# 07_-_5V_VOLTAGE_REGULATOR.net
KiCad netlist of a schematic drawn in Altium Designer
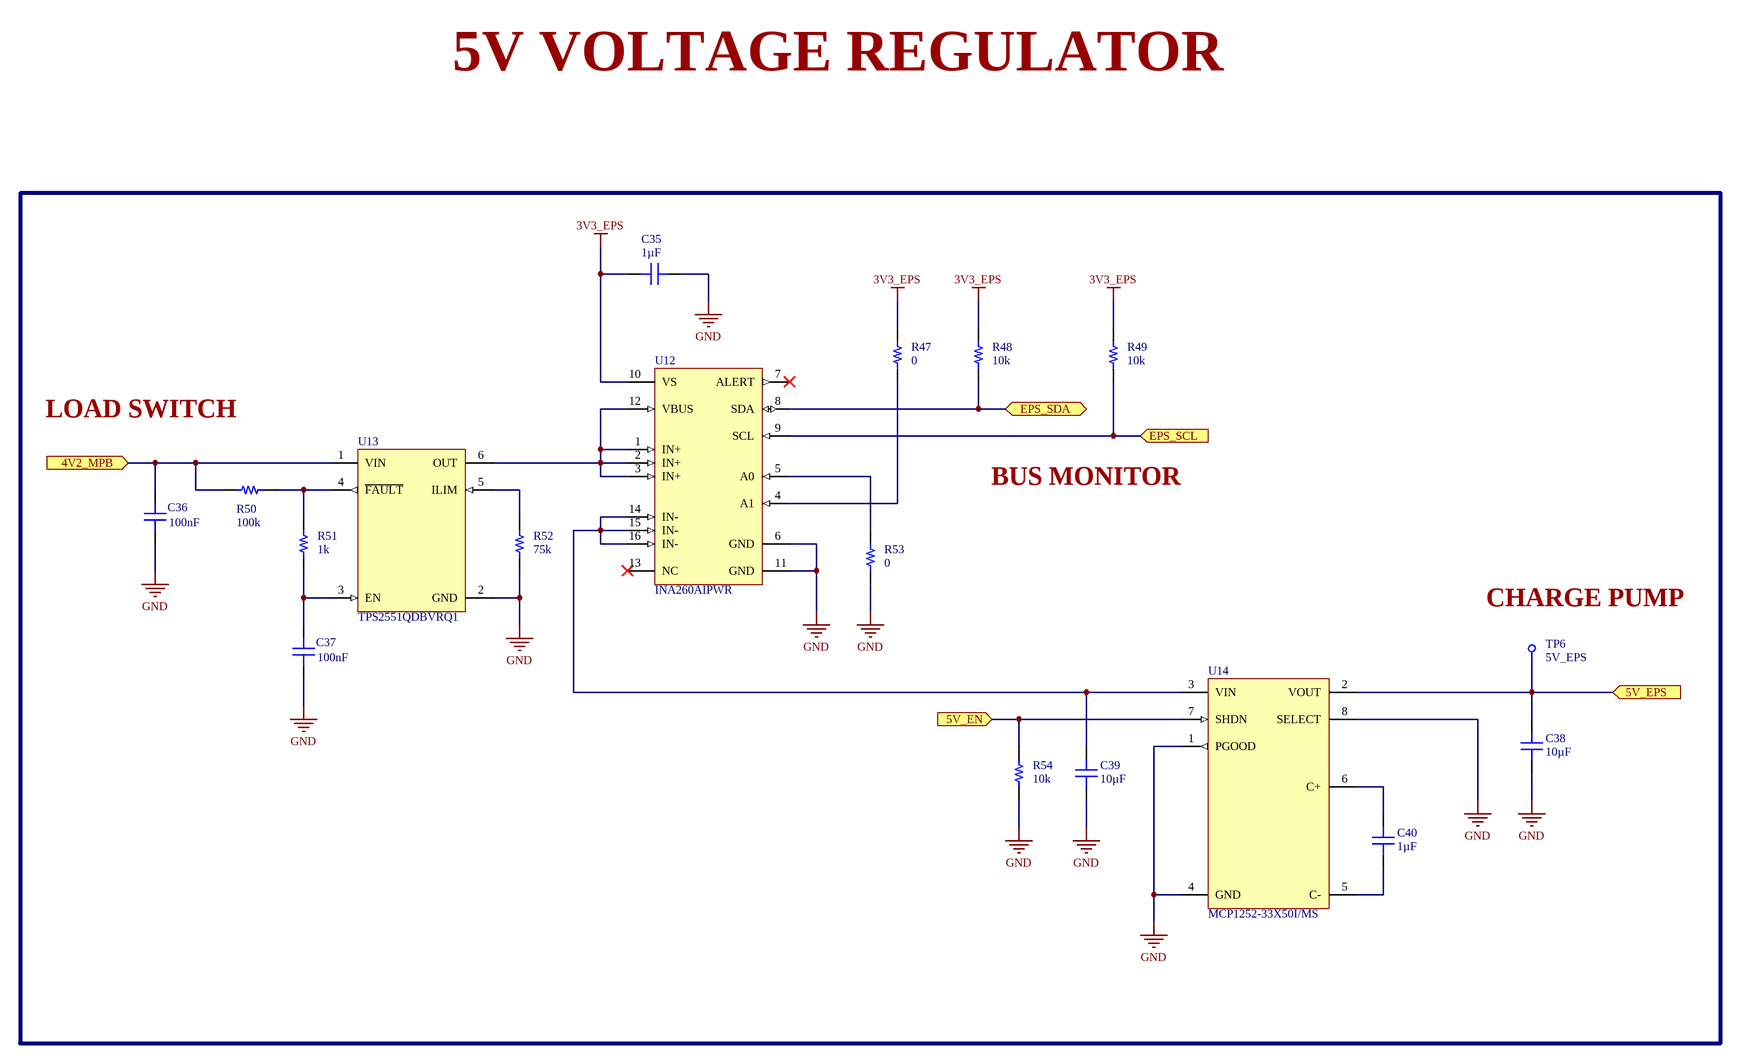
[diagram p0: [07] - 5V VOLTAGE REGULATOR.SchDoc]

(export (version "E")
  (design (tool "Eeschema 10.0.6"))
  (components
    (comp (ref "C35")
      (value "CL10A105KP8NNNC")
      (footprint "CAP 0603/1608")
      (description "CAP CER 1UF 10V X5R 0603")
      (fields
        (field (name "MANUFACTURER") "Samsung")
        (field (name "TOLERANCE") "10%")
        (field (name "CAPACITANCE") "1µF")
      )
      (libsource (lib "UVG") (part "CL10A105KP8NNNC"))
    )
    (comp (ref "C36")
      (value "C0603C104K8RACTU")
      (footprint "CAP 0603/1608")
      (description "CAP CER 0.1UF 10V X7R 0603")
      (fields
        (field (name "MANUFACTURER") "KEMET")
        (field (name "CAPACITANCE") "100nF")
        (field (name "TOLERANCE") "10%")
      )
      (libsource (lib "UVG") (part "C0603C104K8RACTU"))
    )
    (comp (ref "C37")
      (value "C0603C104K8RACTU")
      (footprint "CAP 0603/1608")
      (description "CAP CER 0.1UF 10V X7R 0603")
      (fields
        (field (name "MANUFACTURER") "KEMET")
        (field (name "CAPACITANCE") "100nF")
        (field (name "TOLERANCE") "10%")
      )
      (libsource (lib "UVG") (part "C0603C104K8RACTU"))
    )
    (comp (ref "C38")
      (value "CL10A106MQ8NNNC")
      (footprint "CAP 0603/1608")
      (description "CAP CER 10UF 6.3V X5R 0603")
      (fields
        (field (name "MANUFACTURER") "Samsung")
        (field (name "CAPACITANCE") "10µF")
        (field (name "TOLERANCE") "20%")
      )
      (libsource (lib "UVG") (part "CL10A106MQ8NNNC"))
    )
    (comp (ref "C39")
      (value "CL10A106MQ8NNNC")
      (footprint "CAP 0603/1608")
      (description "CAP CER 10UF 6.3V X5R 0603")
      (fields
        (field (name "MANUFACTURER") "Samsung")
        (field (name "CAPACITANCE") "10µF")
        (field (name "TOLERANCE") "20%")
      )
      (libsource (lib "UVG") (part "CL10A106MQ8NNNC"))
    )
    (comp (ref "C40")
      (value "CL10A105KP8NNNC")
      (footprint "CAP 0603/1608")
      (description "CAP CER 1UF 10V X5R 0603")
      (fields
        (field (name "MANUFACTURER") "Samsung")
        (field (name "TOLERANCE") "10%")
        (field (name "CAPACITANCE") "1µF")
      )
      (libsource (lib "UVG") (part "CL10A105KP8NNNC"))
    )
    (comp (ref "R47")
      (value "RMCF0603ZT0R00")
      (footprint "RES 0603/1608")
      (description "RES SMD 0 OHM JUMPER 1/10W 0603")
      (fields (field (name "MANUFACTURER") "Stackpole Electronics") (field (name "RESISTANCE") "0"))
      (libsource (lib "UVG") (part "RMCF0603ZT0R00"))
    )
    (comp (ref "R48")
      (value "RNCP0603FTD10K0")
      (footprint "RES 0603/1608")
      (description "RES SMD 10K OHM 1% 1/8W 0603")
      (fields
        (field (name "MANUFACTURER") "Stackpole Electronics")
        (field (name "RESISTANCE") "10k")
        (field (name "TOLERANCE") "1%")
      )
      (libsource (lib "UVG") (part "RNCP0603FTD10K0"))
    )
    (comp (ref "R49")
      (value "RNCP0603FTD10K0")
      (footprint "RES 0603/1608")
      (description "RES SMD 10K OHM 1% 1/8W 0603")
      (fields
        (field (name "MANUFACTURER") "Stackpole Electronics")
        (field (name "RESISTANCE") "10k")
        (field (name "TOLERANCE") "1%")
      )
      (libsource (lib "UVG") (part "RNCP0603FTD10K0"))
    )
    (comp (ref "R50")
      (value "CR0603-JW-104ELF")
      (footprint "RES 0603/1608")
      (description "RES SMD 100K OHM 5% 1/10W 0603")
      (fields
        (field (name "MANUFACTURER") "Bourns")
        (field (name "RESISTANCE") "100k")
        (field (name "TOLERANCE") "5%")
      )
      (libsource (lib "UVG") (part "CR0603-JW-104ELF"))
    )
    (comp (ref "R51")
      (value "ESR03EZPJ102")
      (footprint "RES 0603/1608")
      (description "RES SMD 1K OHM 5% 1/4W 0603")
      (fields
        (field (name "MANUFACTURER") "Rohm")
        (field (name "RESISTANCE") "1k")
        (field (name "TOLERANCE") "5%")
      )
      (libsource (lib "UVG") (part "ESR03EZPJ102"))
    )
    (comp (ref "R52")
      (value "ERJ3EKF7502V")
      (footprint "RES 0603/1608")
      (description "RES SMD 75K OHM 1% 1/10W 0603")
      (fields
        (field (name "MANUFACTURER") "Panasonic")
        (field (name "RESISTANCE") "75k")
        (field (name "TOLERANCE") "1%")
      )
      (libsource (lib "UVG") (part "ERJ3EKF7502V"))
    )
    (comp (ref "R53")
      (value "RMCF0603ZT0R00")
      (footprint "RES 0603/1608")
      (description "RES SMD 0 OHM JUMPER 1/10W 0603")
      (fields (field (name "MANUFACTURER") "Stackpole Electronics") (field (name "RESISTANCE") "0"))
      (libsource (lib "UVG") (part "RMCF0603ZT0R00"))
    )
    (comp (ref "R54")
      (value "RNCP0603FTD10K0")
      (footprint "RES 0603/1608")
      (description "RES SMD 10K OHM 1% 1/8W 0603")
      (fields
        (field (name "MANUFACTURER") "Stackpole Electronics")
        (field (name "RESISTANCE") "10k")
        (field (name "TOLERANCE") "1%")
      )
      (libsource (lib "UVG") (part "RNCP0603FTD10K0"))
    )
    (comp (ref "TP6")
      (value "5V_EPS")
      (footprint "Testpoint")
      (description "GENERIC TESTPOINT")
      (libsource (lib "UVG") (part "TESTPOINT"))
    )
    (comp (ref "U12")
      (value "INA260AIPWR")
      (footprint "TSOP65P640X120-16N")
      (description "IC MONITOR PWR/CURR 16TSSOP")
      (fields (field (name "MANUFACTURER") "Texas Instruments"))
      (libsource (lib "UVG") (part "INA260AIPWR"))
    )
    (comp (ref "U13")
      (value "TPS2551QDBVRQ1")
      (footprint "SOT23-6")
      (description "IC POWER-DIST SWITCH ADJ SOT23-6")
      (fields (field (name "MANUFACTURER") "Texas Instruments"))
      (libsource (lib "UVG") (part "TPS2551QDBVRQ1"))
    )
    (comp (ref "U14")
      (value "MCP1252-33X50I/MS")
      (footprint "8-MSOP")
      (description "IC REG SWITCHD CAP PROG 8MSOP")
      (fields (field (name "MANUFACTURER") "Microchip"))
      (libsource (lib "UVG") (part "MCP1252-33X50I/MS"))
    )
  )
  (nets
    (net (code "1") (name "/4V2_MPB") (class "Default")
      (node (ref "C36") (pin "2") (pinfunction "2_2") (pintype "passive"))
      (node (ref "R50") (pin "1") (pinfunction "1_1") (pintype "passive"))
      (node (ref "U13") (pin "1") (pinfunction "VIN_1") (pintype "power_in"))
    )
    (net (code "2") (name "/5V_EN") (class "Default")
      (node (ref "R54") (pin "2") (pinfunction "2_2") (pintype "passive"))
      (node (ref "U14") (pin "7") (pinfunction "SHDN_7") (pintype "input"))
    )
    (net (code "3") (name "/5V_EPS") (class "Default")
      (node (ref "C38") (pin "2") (pinfunction "2_2") (pintype "passive"))
      (node (ref "TP6") (pin "1") (pinfunction "1_1") (pintype "passive"))
      (node (ref "U14") (pin "2") (pinfunction "VOUT_2") (pintype "power_in"))
    )
    (net (code "4") (name "/EPS_SCL") (class "Default")
      (node (ref "R49") (pin "1") (pinfunction "1_1") (pintype "passive"))
      (node (ref "U12") (pin "9") (pinfunction "SCL_9") (pintype "input"))
    )
    (net (code "5") (name "/EPS_SDA") (class "Default")
      (node (ref "R48") (pin "1") (pinfunction "1_1") (pintype "passive"))
      (node (ref "U12") (pin "8") (pinfunction "SDA_8") (pintype "bidirectional"))
    )
    (net (code "6") (name "3V3_EPS") (class "Default")
      (node (ref "C35") (pin "1") (pinfunction "1_1") (pintype "passive"))
      (node (ref "R47") (pin "2") (pinfunction "2_2") (pintype "passive"))
      (node (ref "R48") (pin "2") (pinfunction "2_2") (pintype "passive"))
      (node (ref "R49") (pin "2") (pinfunction "2_2") (pintype "passive"))
      (node (ref "U12") (pin "10") (pinfunction "VS_10") (pintype "power_in"))
    )
    (net (code "7") (name "GND") (class "Default")
      (node (ref "C35") (pin "2") (pinfunction "2_2") (pintype "passive"))
      (node (ref "C36") (pin "1") (pinfunction "1_1") (pintype "passive"))
      (node (ref "C37") (pin "1") (pinfunction "1_1") (pintype "passive"))
      (node (ref "C38") (pin "1") (pinfunction "1_1") (pintype "passive"))
      (node (ref "C39") (pin "1") (pinfunction "1_1") (pintype "passive"))
      (node (ref "R52") (pin "1") (pinfunction "1_1") (pintype "passive"))
      (node (ref "R53") (pin "1") (pinfunction "1_1") (pintype "passive"))
      (node (ref "R54") (pin "1") (pinfunction "1_1") (pintype "passive"))
      (node (ref "U12") (pin "11") (pinfunction "GND_11") (pintype "power_in"))
      (node (ref "U12") (pin "6") (pinfunction "GND_6") (pintype "power_in"))
      (node (ref "U13") (pin "2") (pinfunction "GND_2") (pintype "power_in"))
      (node (ref "U14") (pin "1") (pinfunction "PGOOD_1") (pintype "output"))
      (node (ref "U14") (pin "4") (pinfunction "GND_4") (pintype "power_in"))
      (node (ref "U14") (pin "8") (pinfunction "SELECT_8") (pintype "power_in"))
    )
    (net (code "8") (name "Net-(U12-A0)") (class "Default")
      (node (ref "R53") (pin "2") (pinfunction "2_2") (pintype "passive"))
      (node (ref "U12") (pin "5") (pinfunction "A0_5") (pintype "input"))
    )
    (net (code "9") (name "Net-(U12-A1)") (class "Default")
      (node (ref "R47") (pin "1") (pinfunction "1_1") (pintype "passive"))
      (node (ref "U12") (pin "4") (pinfunction "A1_4") (pintype "input"))
    )
    (net (code "10") (name "Net-(U12-VBUS)") (class "Default")
      (node (ref "U12") (pin "1") (pinfunction "IN+_1") (pintype "input"))
      (node (ref "U12") (pin "12") (pinfunction "VBUS_12") (pintype "input"))
      (node (ref "U12") (pin "2") (pinfunction "IN+_2") (pintype "input"))
      (node (ref "U12") (pin "3") (pinfunction "IN+_3") (pintype "input"))
      (node (ref "U13") (pin "6") (pinfunction "OUT_6") (pintype "power_in"))
    )
    (net (code "11") (name "Net-(U13-EN)") (class "Default")
      (node (ref "C37") (pin "2") (pinfunction "2_2") (pintype "passive"))
      (node (ref "R51") (pin "1") (pinfunction "1_1") (pintype "passive"))
      (node (ref "U13") (pin "3") (pinfunction "EN_3") (pintype "input"))
    )
    (net (code "12") (name "Net-(U13-ILIM)") (class "Default")
      (node (ref "R52") (pin "2") (pinfunction "2_2") (pintype "passive"))
      (node (ref "U13") (pin "5") (pinfunction "ILIM_5") (pintype "input"))
    )
    (net (code "13") (name "Net-(U13-~{FAULT})") (class "Default")
      (node (ref "R50") (pin "2") (pinfunction "2_2") (pintype "passive"))
      (node (ref "R51") (pin "2") (pinfunction "2_2") (pintype "passive"))
      (node (ref "U13") (pin "4") (pinfunction "~{FAULT}_4") (pintype "output"))
    )
    (net (code "14") (name "Net-(U14-C+)") (class "Default")
      (node (ref "C40") (pin "2") (pinfunction "2_2") (pintype "passive"))
      (node (ref "U14") (pin "6") (pinfunction "C+_6") (pintype "passive"))
    )
    (net (code "15") (name "Net-(U14-C-)") (class "Default")
      (node (ref "C40") (pin "1") (pinfunction "1_1") (pintype "passive"))
      (node (ref "U14") (pin "5") (pinfunction "C-_5") (pintype "passive"))
    )
    (net (code "16") (name "Net-(U14-VIN)") (class "Default")
      (node (ref "C39") (pin "2") (pinfunction "2_2") (pintype "passive"))
      (node (ref "U12") (pin "14") (pinfunction "IN-_14") (pintype "input"))
      (node (ref "U12") (pin "15") (pinfunction "IN-_15") (pintype "input"))
      (node (ref "U12") (pin "16") (pinfunction "IN-_16") (pintype "input"))
      (node (ref "U14") (pin "3") (pinfunction "VIN_3") (pintype "power_in"))
    )
    (net (code "17") (name "unconnected-(U12-ALERT-Pad7)") (class "Default")
      (node (ref "U12") (pin "7") (pinfunction "ALERT_7") (pintype "output+no_connect"))
    )
    (net (code "18") (name "unconnected-(U12-NC-Pad13)") (class "Default")
      (node (ref "U12") (pin "13") (pinfunction "NC_13") (pintype "passive+no_connect"))
    )
  )
)
